# SERVOS-2.net
KiCad netlist of a schematic drawn in EAGLE
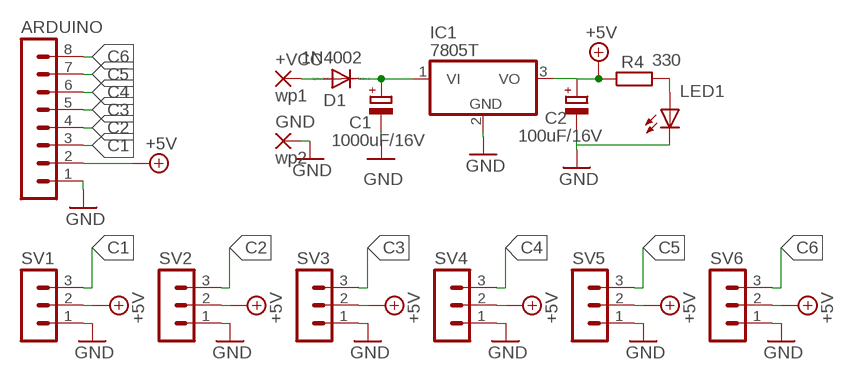
[diagram p0: schematic, sheet 1]

(export (version "E")
  (design (tool "Eeschema 10.0.6"))
  (components
    (comp (ref "+VCC")
      (value "wp1")
      (footprint "eagle-import:1,6_0,9")
      (libsource (lib "eagle-import") (part "WIREPAD1,6/0,9"))
    )
    (comp (ref "ARDUINO")
      (value "MA08-1")
      (footprint "eagle-import:MA08-1")
      (libsource (lib "eagle-import") (part "MA08-1"))
    )
    (comp (ref "C1")
      (value "1000uF/16V")
      (footprint "eagle-import:E2,5-7")
      (libsource (lib "eagle-import") (part "CPOL-EUE2.5-7"))
    )
    (comp (ref "C2")
      (value "100uF/16V")
      (footprint "eagle-import:E2,5-5")
      (libsource (lib "eagle-import") (part "CPOL-EUE2.5-5"))
    )
    (comp (ref "D1")
      (value "1N4002")
      (footprint "eagle-import:DO35-7")
      (libsource (lib "eagle-import") (part "1N4148DO35-7"))
    )
    (comp (ref "GND")
      (value "wp2")
      (footprint "eagle-import:1,6_0,9")
      (libsource (lib "eagle-import") (part "WIREPAD1,6/0,9"))
    )
    (comp (ref "IC1")
      (value "7805T")
      (footprint "eagle-import:TO220H")
      (libsource (lib "eagle-import") (part "78T05"))
    )
    (comp (ref "LED1")
      (value "LED3MM")
      (footprint "eagle-import:LED3MM")
      (libsource (lib "eagle-import") (part "LED3MM"))
    )
    (comp (ref "R4")
      (value "330")
      (footprint "eagle-import:0207_10")
      (libsource (lib "eagle-import") (part "R-EU_0207/10"))
    )
    (comp (ref "SV1")
      (value "MA03-1")
      (footprint "eagle-import:MA03-1")
      (libsource (lib "eagle-import") (part "MA03-1"))
    )
    (comp (ref "SV2")
      (value "MA03-1")
      (footprint "eagle-import:MA03-1")
      (libsource (lib "eagle-import") (part "MA03-1"))
    )
    (comp (ref "SV3")
      (value "MA03-1")
      (footprint "eagle-import:MA03-1")
      (libsource (lib "eagle-import") (part "MA03-1"))
    )
    (comp (ref "SV4")
      (value "MA03-1")
      (footprint "eagle-import:MA03-1")
      (libsource (lib "eagle-import") (part "MA03-1"))
    )
    (comp (ref "SV5")
      (value "MA03-1")
      (footprint "eagle-import:MA03-1")
      (libsource (lib "eagle-import") (part "MA03-1"))
    )
    (comp (ref "SV6")
      (value "MA03-1")
      (footprint "eagle-import:MA03-1")
      (libsource (lib "eagle-import") (part "MA03-1"))
    )
  )
  (nets
    (net (code "1") (name "+5V") (class "Default")
      (node (ref "ARDUINO") (pin "2") (pinfunction "2_2") (pintype "passive"))
      (node (ref "C2") (pin "+") (pinfunction "+_+") (pintype "passive"))
      (node (ref "IC1") (pin "3") (pinfunction "VO_3") (pintype "passive"))
      (node (ref "R4") (pin "1") (pinfunction "1_1") (pintype "passive"))
      (node (ref "SV1") (pin "2") (pinfunction "2_2") (pintype "passive"))
      (node (ref "SV2") (pin "2") (pinfunction "2_2") (pintype "passive"))
      (node (ref "SV3") (pin "2") (pinfunction "2_2") (pintype "passive"))
      (node (ref "SV4") (pin "2") (pinfunction "2_2") (pintype "passive"))
      (node (ref "SV5") (pin "2") (pinfunction "2_2") (pintype "passive"))
      (node (ref "SV6") (pin "2") (pinfunction "2_2") (pintype "passive"))
    )
    (net (code "2") (name "C1") (class "Default")
      (node (ref "ARDUINO") (pin "3") (pinfunction "3_3") (pintype "passive"))
      (node (ref "SV1") (pin "3") (pinfunction "3_3") (pintype "passive"))
    )
    (net (code "3") (name "C2") (class "Default")
      (node (ref "ARDUINO") (pin "4") (pinfunction "4_4") (pintype "passive"))
      (node (ref "SV2") (pin "3") (pinfunction "3_3") (pintype "passive"))
    )
    (net (code "4") (name "C3") (class "Default")
      (node (ref "ARDUINO") (pin "5") (pinfunction "5_5") (pintype "passive"))
      (node (ref "SV3") (pin "3") (pinfunction "3_3") (pintype "passive"))
    )
    (net (code "5") (name "C4") (class "Default")
      (node (ref "ARDUINO") (pin "6") (pinfunction "6_6") (pintype "passive"))
      (node (ref "SV4") (pin "3") (pinfunction "3_3") (pintype "passive"))
    )
    (net (code "6") (name "C5") (class "Default")
      (node (ref "ARDUINO") (pin "7") (pinfunction "7_7") (pintype "passive"))
      (node (ref "SV5") (pin "3") (pinfunction "3_3") (pintype "passive"))
    )
    (net (code "7") (name "C6") (class "Default")
      (node (ref "ARDUINO") (pin "8") (pinfunction "8_8") (pintype "passive"))
      (node (ref "SV6") (pin "3") (pinfunction "3_3") (pintype "passive"))
    )
    (net (code "8") (name "GND") (class "Default")
      (node (ref "ARDUINO") (pin "1") (pinfunction "1_1") (pintype "passive"))
      (node (ref "C1") (pin "-") (pinfunction "-_-") (pintype "passive"))
      (node (ref "C2") (pin "-") (pinfunction "-_-") (pintype "passive"))
      (node (ref "GND") (pin "1") (pinfunction "P_1") (pintype "passive"))
      (node (ref "IC1") (pin "2") (pinfunction "GND_2") (pintype "passive"))
      (node (ref "LED1") (pin "K") (pinfunction "C_K") (pintype "passive"))
      (node (ref "SV1") (pin "1") (pinfunction "1_1") (pintype "passive"))
      (node (ref "SV2") (pin "1") (pinfunction "1_1") (pintype "passive"))
      (node (ref "SV3") (pin "1") (pinfunction "1_1") (pintype "passive"))
      (node (ref "SV4") (pin "1") (pinfunction "1_1") (pintype "passive"))
      (node (ref "SV5") (pin "1") (pinfunction "1_1") (pintype "passive"))
      (node (ref "SV6") (pin "1") (pinfunction "1_1") (pintype "passive"))
    )
    (net (code "9") (name "Net-(+VCC-P)") (class "Default")
      (node (ref "+VCC") (pin "1") (pinfunction "P_1") (pintype "passive"))
      (node (ref "D1") (pin "A") (pinfunction "A_A") (pintype "passive"))
    )
    (net (code "10") (name "Net-(IC1-VI)") (class "Default")
      (node (ref "C1") (pin "+") (pinfunction "+_+") (pintype "passive"))
      (node (ref "D1") (pin "C") (pinfunction "C_C") (pintype "passive"))
      (node (ref "IC1") (pin "1") (pinfunction "VI_1") (pintype "input"))
    )
    (net (code "11") (name "Net-(LED1-PadA)") (class "Default")
      (node (ref "LED1") (pin "A") (pinfunction "A_A") (pintype "passive"))
      (node (ref "R4") (pin "2") (pinfunction "2_2") (pintype "passive"))
    )
  )
)
